# AGC_AD8317_ADL5330.net
KiCad netlist of a schematic drawn in Altium Designer
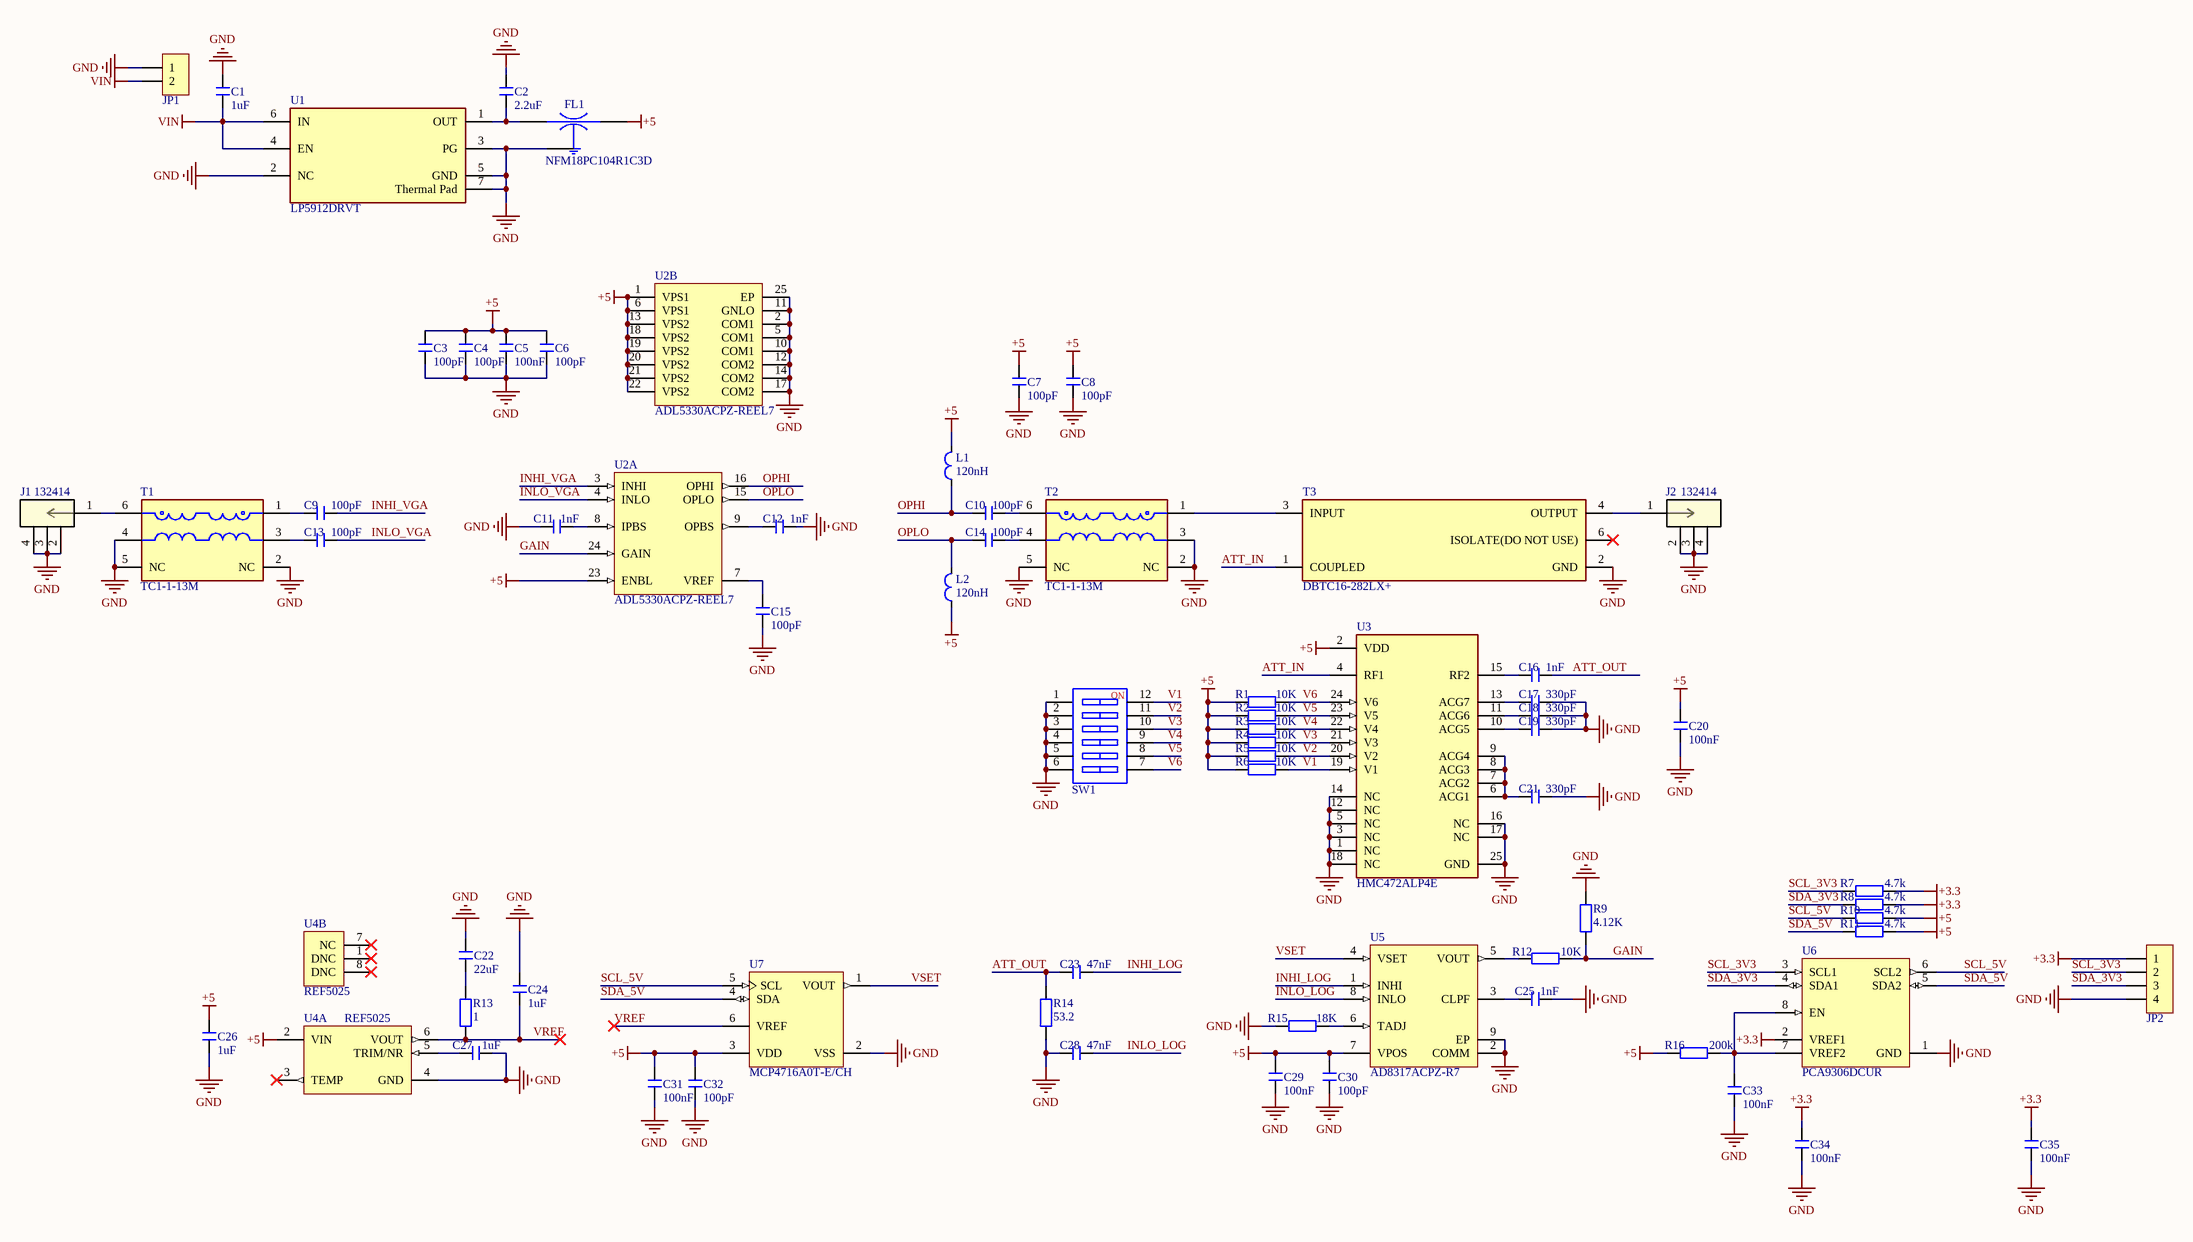
[diagram p0: AGC_AD8317_ADL5330.SchDoc]

(export (version "E")
  (design (tool "Eeschema 10.0.6"))
  (components
    (comp (ref "C1")
      (value "1uF")
      (footprint "C 0402_L")
      (description "贴片电容")
      (libsource (lib "01 - 电容-电阻-电感") (part "C"))
    )
    (comp (ref "C2")
      (value "2.2uF")
      (footprint "C 0603_L")
      (description "贴片电容")
      (libsource (lib "01 - 电容-电阻-电感") (part "C"))
    )
    (comp (ref "C3")
      (value "100pF")
      (footprint "C 0402_L")
      (description "贴片电容")
      (libsource (lib "01 - 电容-电阻-电感") (part "C"))
    )
    (comp (ref "C4")
      (value "100pF")
      (footprint "C 0402_L")
      (description "贴片电容")
      (libsource (lib "01 - 电容-电阻-电感") (part "C"))
    )
    (comp (ref "C5")
      (value "100nF")
      (footprint "C 0402_L")
      (description "贴片电容")
      (libsource (lib "01 - 电容-电阻-电感") (part "C"))
    )
    (comp (ref "C6")
      (value "100pF")
      (footprint "C 0402_L")
      (description "贴片电容")
      (libsource (lib "01 - 电容-电阻-电感") (part "C"))
    )
    (comp (ref "C7")
      (value "100pF")
      (footprint "C 0402_L")
      (description "贴片电容")
      (libsource (lib "01 - 电容-电阻-电感") (part "C"))
    )
    (comp (ref "C8")
      (value "100pF")
      (footprint "C 0402_L")
      (description "贴片电容")
      (libsource (lib "01 - 电容-电阻-电感") (part "C"))
    )
    (comp (ref "C9")
      (value "100pF")
      (footprint "C 0402_L")
      (description "贴片电容")
      (libsource (lib "01 - 电容-电阻-电感") (part "C"))
    )
    (comp (ref "C10")
      (value "100pF")
      (footprint "C 0402_L")
      (description "贴片电容")
      (libsource (lib "01 - 电容-电阻-电感") (part "C"))
    )
    (comp (ref "C11")
      (value "1nF")
      (footprint "C 0402_L")
      (description "贴片电容")
      (libsource (lib "01 - 电容-电阻-电感") (part "C"))
    )
    (comp (ref "C12")
      (value "1nF")
      (footprint "C 0402_L")
      (description "贴片电容")
      (libsource (lib "01 - 电容-电阻-电感") (part "C"))
    )
    (comp (ref "C13")
      (value "100pF")
      (footprint "C 0402_L")
      (description "贴片电容")
      (libsource (lib "01 - 电容-电阻-电感") (part "C"))
    )
    (comp (ref "C14")
      (value "100pF")
      (footprint "C 0402_L")
      (description "贴片电容")
      (libsource (lib "01 - 电容-电阻-电感") (part "C"))
    )
    (comp (ref "C15")
      (value "100pF")
      (footprint "C 0402_L")
      (description "贴片电容")
      (libsource (lib "01 - 电容-电阻-电感") (part "C"))
    )
    (comp (ref "C16")
      (value "1nF")
      (footprint "C 0402_L")
      (description "贴片电容")
      (libsource (lib "01 - 电容-电阻-电感") (part "C"))
    )
    (comp (ref "C17")
      (value "330pF")
      (footprint "C 0402_L")
      (description "贴片电容")
      (libsource (lib "01 - 电容-电阻-电感") (part "C"))
    )
    (comp (ref "C18")
      (value "330pF")
      (footprint "C 0402_L")
      (description "贴片电容")
      (libsource (lib "01 - 电容-电阻-电感") (part "C"))
    )
    (comp (ref "C19")
      (value "330pF")
      (footprint "C 0402_L")
      (description "贴片电容")
      (libsource (lib "01 - 电容-电阻-电感") (part "C"))
    )
    (comp (ref "C20")
      (value "100nF")
      (footprint "C 0402_L")
      (description "贴片电容")
      (libsource (lib "01 - 电容-电阻-电感") (part "C"))
    )
    (comp (ref "C21")
      (value "330pF")
      (footprint "C 0402_L")
      (description "贴片电容")
      (libsource (lib "01 - 电容-电阻-电感") (part "C"))
    )
    (comp (ref "C22")
      (value "22uF")
      (footprint "C 1210_L")
      (description "贴片电容")
      (libsource (lib "01 - 电容-电阻-电感") (part "C"))
    )
    (comp (ref "C23")
      (value "47nF")
      (footprint "C 0402_L")
      (description "贴片电容")
      (libsource (lib "01 - 电容-电阻-电感") (part "C"))
    )
    (comp (ref "C24")
      (value "1uF")
      (footprint "C 0402_L")
      (description "贴片电容")
      (libsource (lib "01 - 电容-电阻-电感") (part "C"))
    )
    (comp (ref "C25")
      (value "1nF")
      (footprint "C 0402_L")
      (description "贴片电容")
      (libsource (lib "01 - 电容-电阻-电感") (part "C"))
    )
    (comp (ref "C26")
      (value "1uF")
      (footprint "C 0402_L")
      (description "贴片电容")
      (libsource (lib "01 - 电容-电阻-电感") (part "C"))
    )
    (comp (ref "C27")
      (value "1uF")
      (footprint "C 0402_L")
      (description "贴片电容")
      (libsource (lib "01 - 电容-电阻-电感") (part "C"))
    )
    (comp (ref "C28")
      (value "47nF")
      (footprint "C 0402_L")
      (description "贴片电容")
      (libsource (lib "01 - 电容-电阻-电感") (part "C"))
    )
    (comp (ref "C29")
      (value "100nF")
      (footprint "C 0402_L")
      (description "贴片电容")
      (libsource (lib "01 - 电容-电阻-电感") (part "C"))
    )
    (comp (ref "C30")
      (value "100pF")
      (footprint "C 0402_L")
      (description "贴片电容")
      (libsource (lib "01 - 电容-电阻-电感") (part "C"))
    )
    (comp (ref "C31")
      (value "100nF")
      (footprint "C 0402_L")
      (description "贴片电容")
      (libsource (lib "01 - 电容-电阻-电感") (part "C"))
    )
    (comp (ref "C32")
      (value "100pF")
      (footprint "C 0402_L")
      (description "贴片电容")
      (libsource (lib "01 - 电容-电阻-电感") (part "C"))
    )
    (comp (ref "C33")
      (value "100nF")
      (footprint "C 0402_L")
      (description "贴片电容")
      (libsource (lib "01 - 电容-电阻-电感") (part "C"))
    )
    (comp (ref "C34")
      (value "100nF")
      (footprint "C 0402_L")
      (description "贴片电容")
      (libsource (lib "01 - 电容-电阻-电感") (part "C"))
    )
    (comp (ref "C35")
      (value "100nF")
      (footprint "C 0402_L")
      (description "贴片电容")
      (libsource (lib "01 - 电容-电阻-电感") (part "C"))
    )
    (comp (ref "FL1")
      (value "NFM18PC104R1C3D")
      (footprint "FIL_NFM18PC104R1C3D")
      (description "SMD Capacitor with Capacitance: 0.10uF Tol. 20%. Rated Voltage: 16Vdc")
      (fields (field (name "MF") "Murata") (field (name "DIGI-KEY_PART_NUMBER") "490-6969-1-ND"))
      (libsource (lib "NFM18PC104R1C3D") (part "NFM18PC104R1C3D"))
    )
    (comp (ref "J1")
      (value "132414")
      (footprint "CONN_132414_AMP")
      (description "No Description Available")
      (fields (field (name "COPYRIGHT") "Copyright (C) 2022 Ultra Librarian. All rights reserved."))
      (libsource (lib "") (part "132414_1"))
    )
    (comp (ref "J2")
      (value "132414")
      (footprint "CONN_132414_AMP")
      (description "No Description Available")
      (fields (field (name "COPYRIGHT") "Copyright (C) 2022 Ultra Librarian. All rights reserved."))
      (libsource (lib "细针大偏脚SMA(用这个)") (part "132414"))
    )
    (comp (ref "JP1")
      (value "HDR-1X2")
      (footprint "KF2510-LI-2P")
      (description "2P接插件")
      (libsource (lib "18 - 接插件-脚距2.54mm (100mil) ") (part "Header 2"))
    )
    (comp (ref "JP2")
      (value "HDR-1X4")
      (footprint "HDR2.54-LI-4P")
      (description "4P接插件")
      (libsource (lib "18 - 接插件-脚距2.54mm (100mil) ") (part "Header 4"))
    )
    (comp (ref "L1")
      (value "120nH")
      (footprint "R 0603_L")
      (description "高频绕线电感")
      (libsource (lib "01 - 电容-电阻-电感") (part "L-Wire"))
    )
    (comp (ref "L2")
      (value "120nH")
      (footprint "R 0603_L")
      (description "高频绕线电感")
      (libsource (lib "01 - 电容-电阻-电感") (part "L-Wire"))
    )
    (comp (ref "R1")
      (value "10K")
      (footprint "R 0402_L")
      (description "贴片电阻")
      (libsource (lib "01 - 电容-电阻-电感") (part "R"))
    )
    (comp (ref "R2")
      (value "10K")
      (footprint "R 0402_L")
      (description "贴片电阻")
      (libsource (lib "01 - 电容-电阻-电感") (part "R"))
    )
    (comp (ref "R3")
      (value "10K")
      (footprint "R 0402_L")
      (description "贴片电阻")
      (libsource (lib "01 - 电容-电阻-电感") (part "R"))
    )
    (comp (ref "R4")
      (value "10K")
      (footprint "R 0402_L")
      (description "贴片电阻")
      (libsource (lib "01 - 电容-电阻-电感") (part "R"))
    )
    (comp (ref "R5")
      (value "10K")
      (footprint "R 0402_L")
      (description "贴片电阻")
      (libsource (lib "01 - 电容-电阻-电感") (part "R"))
    )
    (comp (ref "R6")
      (value "10K")
      (footprint "R 0402_L")
      (description "贴片电阻")
      (libsource (lib "01 - 电容-电阻-电感") (part "R"))
    )
    (comp (ref "R7")
      (value "4.7k")
      (footprint "R 0402_L")
      (description "贴片电阻")
      (libsource (lib "01 - 电容-电阻-电感") (part "R"))
    )
    (comp (ref "R8")
      (value "4.7k")
      (footprint "R 0402_L")
      (description "贴片电阻")
      (libsource (lib "01 - 电容-电阻-电感") (part "R"))
    )
    (comp (ref "R9")
      (value "4.12K")
      (footprint "R 0402_L")
      (description "贴片电阻")
      (libsource (lib "01 - 电容-电阻-电感") (part "R"))
    )
    (comp (ref "R10")
      (value "4.7k")
      (footprint "R 0402_L")
      (description "贴片电阻")
      (libsource (lib "01 - 电容-电阻-电感") (part "R"))
    )
    (comp (ref "R11")
      (value "4.7k")
      (footprint "R 0402_L")
      (description "贴片电阻")
      (libsource (lib "01 - 电容-电阻-电感") (part "R"))
    )
    (comp (ref "R12")
      (value "10K")
      (footprint "R 0402_L")
      (description "贴片电阻")
      (libsource (lib "01 - 电容-电阻-电感") (part "R"))
    )
    (comp (ref "R13")
      (value "1")
      (footprint "R 0402_L")
      (description "贴片电阻")
      (libsource (lib "01 - 电容-电阻-电感") (part "R"))
    )
    (comp (ref "R14")
      (value "53.2")
      (footprint "R 0402_L")
      (description "贴片电阻")
      (libsource (lib "01 - 电容-电阻-电感") (part "R"))
    )
    (comp (ref "R15")
      (value "18K")
      (footprint "R 0402_L")
      (description "贴片电阻")
      (libsource (lib "01 - 电容-电阻-电感") (part "R"))
    )
    (comp (ref "R16")
      (value "200k")
      (footprint "R 0402_L")
      (description "贴片电阻")
      (libsource (lib "01 - 电容-电阻-电感") (part "R"))
    )
    (comp (ref "SW1")
      (value "SW-6P")
      (footprint "CSW1.27 SMD-6P")
      (description "6路编码开关")
      (libsource (lib "03 - 按键-开关-晶振-蜂鸣器") (part "SW-6P"))
    )
    (comp (ref "T1")
      (value "TC1-1-13M")
      (footprint "FP-TC1-1-13M+-MFG")
      (description "RF Transformer 1: 1 5 Terminal SMD")
      (libsource (lib "TC1-1-13M+") (part "TC1-1-13M"))
    )
    (comp (ref "T2")
      (value "TC1-1-13M")
      (footprint "FP-TC1-1-13M+-MFG")
      (description "RF Transformer 1: 1 5 Terminal SMD")
      (libsource (lib "TC1-1-13M+") (part "TC1-1-13M"))
    )
    (comp (ref "T3")
      (value "DBTC16-282LX+")
      (footprint "FP-DBTC16-282LX+-MFG")
      (description "16.8 dB SMT Directional Coupler, 5 - 2850 MHz, 50Ω")
      (libsource (lib "DBTC16-282LX+") (part "DBTC16-282LX+"))
    )
    (comp (ref "U1")
      (value "LP5912DRVT")
      (footprint "FP-DRV0006A-MFG")
      (description "IC REG LINEAR 500MA 6SON")
      (libsource (lib "LP5912") (part "LP5912DRVT"))
    )
    (comp (ref "U2")
      (value "ADL5330ACPZ-REEL7")
      (footprint "ADI-CP-24-2_L")
      (description "10 MHz to 3 GHz VGA with 60 dB Gain Control Range, 3GHz, CP-24-2, 1500 Reel, Pb-Free")
      (libsource (lib "ADL5330ACPZ") (part "ADL5330ACPZ"))
    )
    (comp (ref "U3")
      (value "HMC472ALP4E")
      (footprint "FP-HMC472ALP4E-IPC_A")
      (description "RF ATTENUATOR 31.5DB 50OHM 24QFN")
      (fields
        (field (name "OCTOPART") "https://octopart.com/hmc472alp4e-analog+devices-51966954")
        (field (name "MANUFACTURER") "Analog Devices")
      )
      (libsource (lib "HMC472ALP4E") (part "HMC472ALP4E"))
    )
    (comp (ref "U4")
      (value "REF5025")
      (footprint "DGK0008A_N")
      (fields (field (name "PARTNUMBER") "REF5025AIDGKT") (field (name "MANUFACTURER") "Texas Instruments"))
      (libsource (lib "REF50") (part "REF50"))
    )
    (comp (ref "U5")
      (value "AD8317ACPZ-R7")
      (footprint "ADI-CP-8-1_L")
      (description "1 MHz to 10 GHz, 55 dB Log Detector/Controller, 6ns Response Time, CP-8-1, Pb-Free, 3000 Reel")
      (libsource (lib "AD8317ACPZ") (part "CMP-0284-00065-1"))
    )
    (comp (ref "U6")
      (value "PCA9306DCUR")
      (footprint "DCU0008A_L")
      (fields (field (name "MANUFACTURER") "Texas Instruments"))
      (libsource (lib "PCA9306DCUR") (part "CMP-0314-00419-2"))
    )
    (comp (ref "U7")
      (value "MCP4716A0T-E/CH")
      (footprint "SOT23-6L")
      (libsource (lib "MCP4716A0T-E") (part "CMP-0188-01210-1"))
    )
  )
  (nets
    (net (code "1") (name "+3.3") (class "Default")
      (node (ref "C34") (pin "2") (pinfunction "2_2") (pintype "passive"))
      (node (ref "C35") (pin "2") (pinfunction "2_2") (pintype "passive"))
      (node (ref "JP2") (pin "1") (pinfunction "1_1") (pintype "passive"))
      (node (ref "R7") (pin "1") (pinfunction "1_1") (pintype "passive"))
      (node (ref "R8") (pin "1") (pinfunction "1_1") (pintype "passive"))
      (node (ref "U6") (pin "2") (pinfunction "VREF1_2") (pintype "power_in"))
    )
    (net (code "2") (name "+5") (class "Default")
      (node (ref "C20") (pin "2") (pinfunction "2_2") (pintype "passive"))
      (node (ref "C26") (pin "2") (pinfunction "2_2") (pintype "passive"))
      (node (ref "C29") (pin "1") (pinfunction "1_1") (pintype "passive"))
      (node (ref "C3") (pin "2") (pinfunction "2_2") (pintype "passive"))
      (node (ref "C30") (pin "1") (pinfunction "1_1") (pintype "passive"))
      (node (ref "C31") (pin "2") (pinfunction "2_2") (pintype "passive"))
      (node (ref "C32") (pin "2") (pinfunction "2_2") (pintype "passive"))
      (node (ref "C4") (pin "2") (pinfunction "2_2") (pintype "passive"))
      (node (ref "C5") (pin "2") (pinfunction "2_2") (pintype "passive"))
      (node (ref "C6") (pin "2") (pinfunction "2_2") (pintype "passive"))
      (node (ref "C7") (pin "2") (pinfunction "2_2") (pintype "passive"))
      (node (ref "C8") (pin "2") (pinfunction "2_2") (pintype "passive"))
      (node (ref "FL1") (pin "3") (pinfunction "OUT_3") (pintype "passive"))
      (node (ref "L1") (pin "2") (pinfunction "2_2") (pintype "passive"))
      (node (ref "L2") (pin "1") (pinfunction "1_1") (pintype "passive"))
      (node (ref "R1") (pin "1") (pinfunction "1_1") (pintype "passive"))
      (node (ref "R10") (pin "1") (pinfunction "1_1") (pintype "passive"))
      (node (ref "R11") (pin "1") (pinfunction "1_1") (pintype "passive"))
      (node (ref "R16") (pin "2") (pinfunction "2_2") (pintype "passive"))
      (node (ref "R2") (pin "1") (pinfunction "1_1") (pintype "passive"))
      (node (ref "R3") (pin "1") (pinfunction "1_1") (pintype "passive"))
      (node (ref "R4") (pin "1") (pinfunction "1_1") (pintype "passive"))
      (node (ref "R5") (pin "1") (pinfunction "1_1") (pintype "passive"))
      (node (ref "R6") (pin "1") (pinfunction "1_1") (pintype "passive"))
      (node (ref "U2") (pin "1") (pinfunction "VPS1_1") (pintype "power_in"))
      (node (ref "U2") (pin "13") (pinfunction "VPS2_13") (pintype "power_in"))
      (node (ref "U2") (pin "18") (pinfunction "VPS2_18") (pintype "power_in"))
      (node (ref "U2") (pin "19") (pinfunction "VPS2_19") (pintype "power_in"))
      (node (ref "U2") (pin "20") (pinfunction "VPS2_20") (pintype "power_in"))
      (node (ref "U2") (pin "21") (pinfunction "VPS2_21") (pintype "power_in"))
      (node (ref "U2") (pin "22") (pinfunction "VPS2_22") (pintype "power_in"))
      (node (ref "U2") (pin "23") (pinfunction "ENBL_23") (pintype "input"))
      (node (ref "U2") (pin "6") (pinfunction "VPS1_6") (pintype "power_in"))
      (node (ref "U3") (pin "2") (pinfunction "VDD_2") (pintype "power_in"))
      (node (ref "U4") (pin "2") (pinfunction "VIN_2") (pintype "power_in"))
      (node (ref "U5") (pin "7") (pinfunction "VPOS_7") (pintype "power_in"))
      (node (ref "U7") (pin "3") (pinfunction "VDD_3") (pintype "power_in"))
    )
    (net (code "3") (name "/ATT_IN") (class "Default")
      (node (ref "T3") (pin "1") (pinfunction "COUPLED_1") (pintype "passive"))
      (node (ref "U3") (pin "4") (pinfunction "RF1_4") (pintype "passive"))
    )
    (net (code "4") (name "/ATT_OUT") (class "Default")
      (node (ref "C16") (pin "2") (pinfunction "2_2") (pintype "passive"))
      (node (ref "C23") (pin "1") (pinfunction "1_1") (pintype "passive"))
      (node (ref "R14") (pin "2") (pinfunction "2_2") (pintype "passive"))
    )
    (net (code "5") (name "/GAIN") (class "Default")
      (node (ref "R12") (pin "1") (pinfunction "1_1") (pintype "passive"))
      (node (ref "R9") (pin "2") (pinfunction "2_2") (pintype "passive"))
      (node (ref "U2") (pin "24") (pinfunction "GAIN_24") (pintype "input"))
    )
    (net (code "6") (name "/INHI_LOG") (class "Default")
      (node (ref "C23") (pin "2") (pinfunction "2_2") (pintype "passive"))
      (node (ref "U5") (pin "1") (pinfunction "INHI_1") (pintype "input"))
    )
    (net (code "7") (name "/INHI_VGA") (class "Default")
      (node (ref "C9") (pin "2") (pinfunction "2_2") (pintype "passive"))
      (node (ref "U2") (pin "3") (pinfunction "INHI_3") (pintype "input"))
    )
    (net (code "8") (name "/INLO_LOG") (class "Default")
      (node (ref "C28") (pin "2") (pinfunction "2_2") (pintype "passive"))
      (node (ref "U5") (pin "8") (pinfunction "INLO_8") (pintype "input"))
    )
    (net (code "9") (name "/INLO_VGA") (class "Default")
      (node (ref "C13") (pin "2") (pinfunction "2_2") (pintype "passive"))
      (node (ref "U2") (pin "4") (pinfunction "INLO_4") (pintype "input"))
    )
    (net (code "10") (name "/OPHI") (class "Default")
      (node (ref "C10") (pin "1") (pinfunction "1_1") (pintype "passive"))
      (node (ref "L1") (pin "1") (pinfunction "1_1") (pintype "passive"))
      (node (ref "U2") (pin "16") (pinfunction "OPHI_16") (pintype "output"))
    )
    (net (code "11") (name "/OPLO") (class "Default")
      (node (ref "C14") (pin "1") (pinfunction "1_1") (pintype "passive"))
      (node (ref "L2") (pin "2") (pinfunction "2_2") (pintype "passive"))
      (node (ref "U2") (pin "15") (pinfunction "OPLO_15") (pintype "output"))
    )
    (net (code "12") (name "/SCL_3V3") (class "Default")
      (node (ref "JP2") (pin "2") (pinfunction "2_2") (pintype "passive"))
      (node (ref "R7") (pin "2") (pinfunction "2_2") (pintype "passive"))
      (node (ref "U6") (pin "3") (pinfunction "SCL1_3") (pintype "input"))
    )
    (net (code "13") (name "/SCL_5V") (class "Default")
      (node (ref "R10") (pin "2") (pinfunction "2_2") (pintype "passive"))
      (node (ref "U6") (pin "6") (pinfunction "SCL2_6") (pintype "output"))
      (node (ref "U7") (pin "5") (pinfunction "SCL_5") (pintype "input"))
    )
    (net (code "14") (name "/SDA_3V3") (class "Default")
      (node (ref "JP2") (pin "3") (pinfunction "3_3") (pintype "passive"))
      (node (ref "R8") (pin "2") (pinfunction "2_2") (pintype "passive"))
      (node (ref "U6") (pin "4") (pinfunction "SDA1_4") (pintype "bidirectional"))
    )
    (net (code "15") (name "/SDA_5V") (class "Default")
      (node (ref "R11") (pin "2") (pinfunction "2_2") (pintype "passive"))
      (node (ref "U6") (pin "5") (pinfunction "SDA2_5") (pintype "bidirectional"))
      (node (ref "U7") (pin "4") (pinfunction "SDA_4") (pintype "bidirectional"))
    )
    (net (code "16") (name "/V1") (class "Default")
      (node (ref "R6") (pin "2") (pinfunction "2_2") (pintype "passive"))
      (node (ref "SW1") (pin "12") (pinfunction "12_12") (pintype "passive"))
      (node (ref "U3") (pin "19") (pinfunction "V1_19") (pintype "input"))
    )
    (net (code "17") (name "/V2") (class "Default")
      (node (ref "R5") (pin "2") (pinfunction "2_2") (pintype "passive"))
      (node (ref "SW1") (pin "11") (pinfunction "11_11") (pintype "passive"))
      (node (ref "U3") (pin "20") (pinfunction "V2_20") (pintype "input"))
    )
    (net (code "18") (name "/V3") (class "Default")
      (node (ref "R4") (pin "2") (pinfunction "2_2") (pintype "passive"))
      (node (ref "SW1") (pin "10") (pinfunction "10_10") (pintype "passive"))
      (node (ref "U3") (pin "21") (pinfunction "V3_21") (pintype "input"))
    )
    (net (code "19") (name "/V4") (class "Default")
      (node (ref "R3") (pin "2") (pinfunction "2_2") (pintype "passive"))
      (node (ref "SW1") (pin "9") (pinfunction "9_9") (pintype "passive"))
      (node (ref "U3") (pin "22") (pinfunction "V4_22") (pintype "input"))
    )
    (net (code "20") (name "/V5") (class "Default")
      (node (ref "R2") (pin "2") (pinfunction "2_2") (pintype "passive"))
      (node (ref "SW1") (pin "8") (pinfunction "8_8") (pintype "passive"))
      (node (ref "U3") (pin "23") (pinfunction "V5_23") (pintype "input"))
    )
    (net (code "21") (name "/V6") (class "Default")
      (node (ref "R1") (pin "2") (pinfunction "2_2") (pintype "passive"))
      (node (ref "SW1") (pin "7") (pinfunction "7_7") (pintype "passive"))
      (node (ref "U3") (pin "24") (pinfunction "V6_24") (pintype "input"))
    )
    (net (code "22") (name "/VREF") (class "Default")
      (node (ref "C24") (pin "1") (pinfunction "1_1") (pintype "passive"))
      (node (ref "R13") (pin "1") (pinfunction "1_1") (pintype "passive"))
      (node (ref "U4") (pin "6") (pinfunction "VOUT_6") (pintype "output"))
      (node (ref "U7") (pin "6") (pinfunction "VREF_6") (pintype "power_in"))
    )
    (net (code "23") (name "/VSET") (class "Default")
      (node (ref "U5") (pin "4") (pinfunction "VSET_4") (pintype "input"))
      (node (ref "U7") (pin "1") (pinfunction "VOUT_1") (pintype "output"))
    )
    (net (code "24") (name "GND") (class "Default")
      (node (ref "C1") (pin "2") (pinfunction "2_2") (pintype "passive"))
      (node (ref "C11") (pin "1") (pinfunction "1_1") (pintype "passive"))
      (node (ref "C12") (pin "1") (pinfunction "1_1") (pintype "passive"))
      (node (ref "C15") (pin "1") (pinfunction "1_1") (pintype "passive"))
      (node (ref "C17") (pin "2") (pinfunction "2_2") (pintype "passive"))
      (node (ref "C18") (pin "2") (pinfunction "2_2") (pintype "passive"))
      (node (ref "C19") (pin "2") (pinfunction "2_2") (pintype "passive"))
      (node (ref "C2") (pin "2") (pinfunction "2_2") (pintype "passive"))
      (node (ref "C20") (pin "1") (pinfunction "1_1") (pintype "passive"))
      (node (ref "C21") (pin "2") (pinfunction "2_2") (pintype "passive"))
      (node (ref "C22") (pin "2") (pinfunction "2_2") (pintype "passive"))
      (node (ref "C24") (pin "2") (pinfunction "2_2") (pintype "passive"))
      (node (ref "C25") (pin "1") (pinfunction "1_1") (pintype "passive"))
      (node (ref "C26") (pin "1") (pinfunction "1_1") (pintype "passive"))
      (node (ref "C27") (pin "2") (pinfunction "2_2") (pintype "passive"))
      (node (ref "C28") (pin "1") (pinfunction "1_1") (pintype "passive"))
      (node (ref "C29") (pin "2") (pinfunction "2_2") (pintype "passive"))
      (node (ref "C3") (pin "1") (pinfunction "1_1") (pintype "passive"))
      (node (ref "C30") (pin "2") (pinfunction "2_2") (pintype "passive"))
      (node (ref "C31") (pin "1") (pinfunction "1_1") (pintype "passive"))
      (node (ref "C32") (pin "1") (pinfunction "1_1") (pintype "passive"))
      (node (ref "C33") (pin "1") (pinfunction "1_1") (pintype "passive"))
      (node (ref "C34") (pin "1") (pinfunction "1_1") (pintype "passive"))
      (node (ref "C35") (pin "1") (pinfunction "1_1") (pintype "passive"))
      (node (ref "C4") (pin "1") (pinfunction "1_1") (pintype "passive"))
      (node (ref "C5") (pin "1") (pinfunction "1_1") (pintype "passive"))
      (node (ref "C6") (pin "1") (pinfunction "1_1") (pintype "passive"))
      (node (ref "C7") (pin "1") (pinfunction "1_1") (pintype "passive"))
      (node (ref "C8") (pin "1") (pinfunction "1_1") (pintype "passive"))
      (node (ref "FL1") (pin "2") (pinfunction "GND_2") (pintype "power_in"))
      (node (ref "J1") (pin "2") (pinfunction "2_2") (pintype "passive"))
      (node (ref "J1") (pin "3") (pinfunction "3_3") (pintype "passive"))
      (node (ref "J1") (pin "4") (pinfunction "4_4") (pintype "passive"))
      (node (ref "J2") (pin "2") (pinfunction "2_2") (pintype "passive"))
      (node (ref "J2") (pin "3") (pinfunction "3_3") (pintype "passive"))
      (node (ref "J2") (pin "4") (pinfunction "4_4") (pintype "passive"))
      (node (ref "JP1") (pin "1") (pinfunction "1_1") (pintype "passive"))
      (node (ref "JP2") (pin "4") (pinfunction "4_4") (pintype "passive"))
      (node (ref "R14") (pin "1") (pinfunction "1_1") (pintype "passive"))
      (node (ref "R15") (pin "1") (pinfunction "1_1") (pintype "passive"))
      (node (ref "R9") (pin "1") (pinfunction "1_1") (pintype "passive"))
      (node (ref "SW1") (pin "1") (pinfunction "1_1") (pintype "passive"))
      (node (ref "SW1") (pin "2") (pinfunction "2_2") (pintype "passive"))
      (node (ref "SW1") (pin "3") (pinfunction "3_3") (pintype "passive"))
      (node (ref "SW1") (pin "4") (pinfunction "4_4") (pintype "passive"))
      (node (ref "SW1") (pin "5") (pinfunction "5_5") (pintype "passive"))
      (node (ref "SW1") (pin "6") (pinfunction "6_6") (pintype "passive"))
      (node (ref "T1") (pin "2") (pinfunction "NC_2") (pintype "passive"))
      (node (ref "T1") (pin "4") (pinfunction "PRIMARY_4") (pintype "passive"))
      (node (ref "T1") (pin "5") (pinfunction "NC_5") (pintype "passive"))
      (node (ref "T2") (pin "2") (pinfunction "NC_2") (pintype "passive"))
      (node (ref "T2") (pin "3") (pinfunction "SECONDARY_3") (pintype "passive"))
      (node (ref "T2") (pin "5") (pinfunction "NC_5") (pintype "passive"))
      (node (ref "T3") (pin "2") (pinfunction "GND_2") (pintype "power_in"))
      (node (ref "U1") (pin "2") (pinfunction "NC_2") (pintype "passive"))
      (node (ref "U1") (pin "3") (pinfunction "PG_3") (pintype "passive"))
      (node (ref "U1") (pin "5") (pinfunction "GND_5") (pintype "power_in"))
      (node (ref "U1") (pin "7") (pinfunction "Thermal_Pad_7") (pintype "power_in"))
      (node (ref "U2") (pin "10") (pinfunction "COM1_10") (pintype "power_in"))
      (node (ref "U2") (pin "11") (pinfunction "GNLO_11") (pintype "power_in"))
      (node (ref "U2") (pin "12") (pinfunction "COM2_12") (pintype "power_in"))
      (node (ref "U2") (pin "14") (pinfunction "COM2_14") (pintype "power_in"))
      (node (ref "U2") (pin "17") (pinfunction "COM2_17") (pintype "power_in"))
      (node (ref "U2") (pin "2") (pinfunction "COM1_2") (pintype "power_in"))
      (node (ref "U2") (pin "25") (pinfunction "EP_25") (pintype "power_in"))
      (node (ref "U2") (pin "5") (pinfunction "COM1_5") (pintype "power_in"))
      (node (ref "U3") (pin "1") (pinfunction "NC_1") (pintype "passive"))
      (node (ref "U3") (pin "12") (pinfunction "NC_12") (pintype "passive"))
      (node (ref "U3") (pin "14") (pinfunction "NC_14") (pintype "passive"))
      (node (ref "U3") (pin "16") (pinfunction "NC_16") (pintype "passive"))
      (node (ref "U3") (pin "17") (pinfunction "NC_17") (pintype "passive"))
      (node (ref "U3") (pin "18") (pinfunction "NC_18") (pintype "passive"))
      (node (ref "U3") (pin "25") (pinfunction "GND_25") (pintype "power_in"))
      (node (ref "U3") (pin "3") (pinfunction "NC_3") (pintype "passive"))
      (node (ref "U3") (pin "5") (pinfunction "NC_5") (pintype "passive"))
      (node (ref "U4") (pin "4") (pinfunction "GND_4") (pintype "power_in"))
      (node (ref "U5") (pin "2") (pinfunction "COMM_2") (pintype "power_in"))
      (node (ref "U5") (pin "9") (pinfunction "EP_9") (pintype "power_in"))
      (node (ref "U6") (pin "1") (pinfunction "GND_1") (pintype "power_in"))
      (node (ref "U7") (pin "2") (pinfunction "VSS_2") (pintype "power_in"))
    )
    (net (code "25") (name "Net-(C22-Pad1)") (class "Default")
      (node (ref "C22") (pin "1") (pinfunction "1_1") (pintype "passive"))
      (node (ref "R13") (pin "2") (pinfunction "2_2") (pintype "passive"))
    )
    (net (code "26") (name "Net-(FL1-IN)") (class "Default")
      (node (ref "C2") (pin "1") (pinfunction "1_1") (pintype "passive"))
      (node (ref "FL1") (pin "1") (pinfunction "IN_1") (pintype "passive"))
      (node (ref "U1") (pin "1") (pinfunction "OUT_1") (pintype "power_in"))
    )
    (net (code "27") (name "Net-(T1-PRIMARY_DOT)") (class "Default")
      (node (ref "J1") (pin "1") (pinfunction "1_1") (pintype "passive"))
      (node (ref "T1") (pin "6") (pinfunction "PRIMARY_DOT_6") (pintype "passive"))
    )
    (net (code "28") (name "Net-(T1-SECONDARY)") (class "Default")
      (node (ref "C13") (pin "1") (pinfunction "1_1") (pintype "passive"))
      (node (ref "T1") (pin "3") (pinfunction "SECONDARY_3") (pintype "passive"))
    )
    (net (code "29") (name "Net-(T1-SECONDARY_DOT)") (class "Default")
      (node (ref "C9") (pin "1") (pinfunction "1_1") (pintype "passive"))
      (node (ref "T1") (pin "1") (pinfunction "SECONDARY_DOT_1") (pintype "passive"))
    )
    (net (code "30") (name "Net-(T2-PRIMARY)") (class "Default")
      (node (ref "C14") (pin "2") (pinfunction "2_2") (pintype "passive"))
      (node (ref "T2") (pin "4") (pinfunction "PRIMARY_4") (pintype "passive"))
    )
    (net (code "31") (name "Net-(T2-PRIMARY_DOT)") (class "Default")
      (node (ref "C10") (pin "2") (pinfunction "2_2") (pintype "passive"))
      (node (ref "T2") (pin "6") (pinfunction "PRIMARY_DOT_6") (pintype "passive"))
    )
    (net (code "32") (name "Net-(T2-SECONDARY_DOT)") (class "Default")
      (node (ref "T2") (pin "1") (pinfunction "SECONDARY_DOT_1") (pintype "passive"))
      (node (ref "T3") (pin "3") (pinfunction "INPUT_3") (pintype "passive"))
    )
    (net (code "33") (name "Net-(T3-OUTPUT)") (class "Default")
      (node (ref "J2") (pin "1") (pinfunction "1_1") (pintype "passive"))
      (node (ref "T3") (pin "4") (pinfunction "OUTPUT_4") (pintype "passive"))
    )
    (net (code "34") (name "Net-(U2A-IPBS)") (class "Default")
      (node (ref "C11") (pin "2") (pinfunction "2_2") (pintype "passive"))
      (node (ref "U2") (pin "8") (pinfunction "IPBS_8") (pintype "input"))
    )
    (net (code "35") (name "Net-(U2A-OPBS)") (class "Default")
      (node (ref "C12") (pin "2") (pinfunction "2_2") (pintype "passive"))
      (node (ref "U2") (pin "9") (pinfunction "OPBS_9") (pintype "output"))
    )
    (net (code "36") (name "Net-(U2A-VREF)") (class "Default")
      (node (ref "C15") (pin "2") (pinfunction "2_2") (pintype "passive"))
      (node (ref "U2") (pin "7") (pinfunction "VREF_7") (pintype "passive"))
    )
    (net (code "37") (name "Net-(U3-ACG1)") (class "Default")
      (node (ref "C21") (pin "1") (pinfunction "1_1") (pintype "passive"))
      (node (ref "U3") (pin "6") (pinfunction "ACG1_6") (pintype "passive"))
      (node (ref "U3") (pin "7") (pinfunction "ACG2_7") (pintype "passive"))
      (node (ref "U3") (pin "8") (pinfunction "ACG3_8") (pintype "passive"))
      (node (ref "U3") (pin "9") (pinfunction "ACG4_9") (pintype "passive"))
    )
    (net (code "38") (name "Net-(U3-ACG5)") (class "Default")
      (node (ref "C19") (pin "1") (pinfunction "1_1") (pintype "passive"))
      (node (ref "U3") (pin "10") (pinfunction "ACG5_10") (pintype "passive"))
    )
    (net (code "39") (name "Net-(U3-ACG6)") (class "Default")
      (node (ref "C18") (pin "1") (pinfunction "1_1") (pintype "passive"))
      (node (ref "U3") (pin "11") (pinfunction "ACG6_11") (pintype "passive"))
    )
    (net (code "40") (name "Net-(U3-ACG7)") (class "Default")
      (node (ref "C17") (pin "1") (pinfunction "1_1") (pintype "passive"))
      (node (ref "U3") (pin "13") (pinfunction "ACG7_13") (pintype "passive"))
    )
    (net (code "41") (name "Net-(U3-RF2)") (class "Default")
      (node (ref "C16") (pin "1") (pinfunction "1_1") (pintype "passive"))
      (node (ref "U3") (pin "15") (pinfunction "RF2_15") (pintype "passive"))
    )
    (net (code "42") (name "Net-(U4A-TRIM{slash}NR)") (class "Default")
      (node (ref "C27") (pin "1") (pinfunction "1_1") (pintype "passive"))
      (node (ref "U4") (pin "5") (pinfunction "TRIM/NR_5") (pintype "input"))
    )
    (net (code "43") (name "Net-(U5-CLPF)") (class "Default")
      (node (ref "C25") (pin "2") (pinfunction "2_2") (pintype "passive"))
      (node (ref "U5") (pin "3") (pinfunction "CLPF_3") (pintype "passive"))
    )
    (net (code "44") (name "Net-(U5-TADJ)") (class "Default")
      (node (ref "R15") (pin "2") (pinfunction "2_2") (pintype "passive"))
      (node (ref "U5") (pin "6") (pinfunction "TADJ_6") (pintype "input"))
    )
    (net (code "45") (name "Net-(U5-VOUT)") (class "Default")
      (node (ref "R12") (pin "2") (pinfunction "2_2") (pintype "passive"))
      (node (ref "U5") (pin "5") (pinfunction "VOUT_5") (pintype "output"))
    )
    (net (code "46") (name "Net-(U6-EN)") (class "Default")
      (node (ref "C33") (pin "2") (pinfunction "2_2") (pintype "passive"))
      (node (ref "R16") (pin "1") (pinfunction "1_1") (pintype "passive"))
      (node (ref "U6") (pin "7") (pinfunction "VREF2_7") (pintype "power_in"))
      (node (ref "U6") (pin "8") (pinfunction "EN_8") (pintype "input"))
    )
    (net (code "47") (name "VIN") (class "Default")
      (node (ref "C1") (pin "1") (pinfunction "1_1") (pintype "passive"))
      (node (ref "JP1") (pin "2") (pinfunction "2_2") (pintype "passive"))
      (node (ref "U1") (pin "4") (pinfunction "EN_4") (pintype "passive"))
      (node (ref "U1") (pin "6") (pinfunction "IN_6") (pintype "power_in"))
    )
    (net (code "48") (name "unconnected-(T3-ISOLATE(DO_NOT_USE)-Pad6)") (class "Default")
      (node (ref "T3") (pin "6") (pinfunction "ISOLATE(DO_NOT_USE)_6") (pintype "passive+no_connect"))
    )
    (net (code "49") (name "unconnected-(U4A-TEMP-Pad3)") (class "Default")
      (node (ref "U4") (pin "3") (pinfunction "TEMP_3") (pintype "output+no_connect"))
    )
    (net (code "50") (name "unconnected-(U4B-DNC-Pad1)") (class "Default")
      (node (ref "U4") (pin "1") (pinfunction "DNC_1") (pintype "passive+no_connect"))
    )
    (net (code "51") (name "unconnected-(U4B-DNC-Pad8)") (class "Default")
      (node (ref "U4") (pin "8") (pinfunction "DNC_8") (pintype "passive+no_connect"))
    )
    (net (code "52") (name "unconnected-(U4B-NC-Pad7)") (class "Default")
      (node (ref "U4") (pin "7") (pinfunction "NC_7") (pintype "passive+no_connect"))
    )
  )
)
